# Connectors.net
KiCad netlist of a schematic drawn in Altium Designer
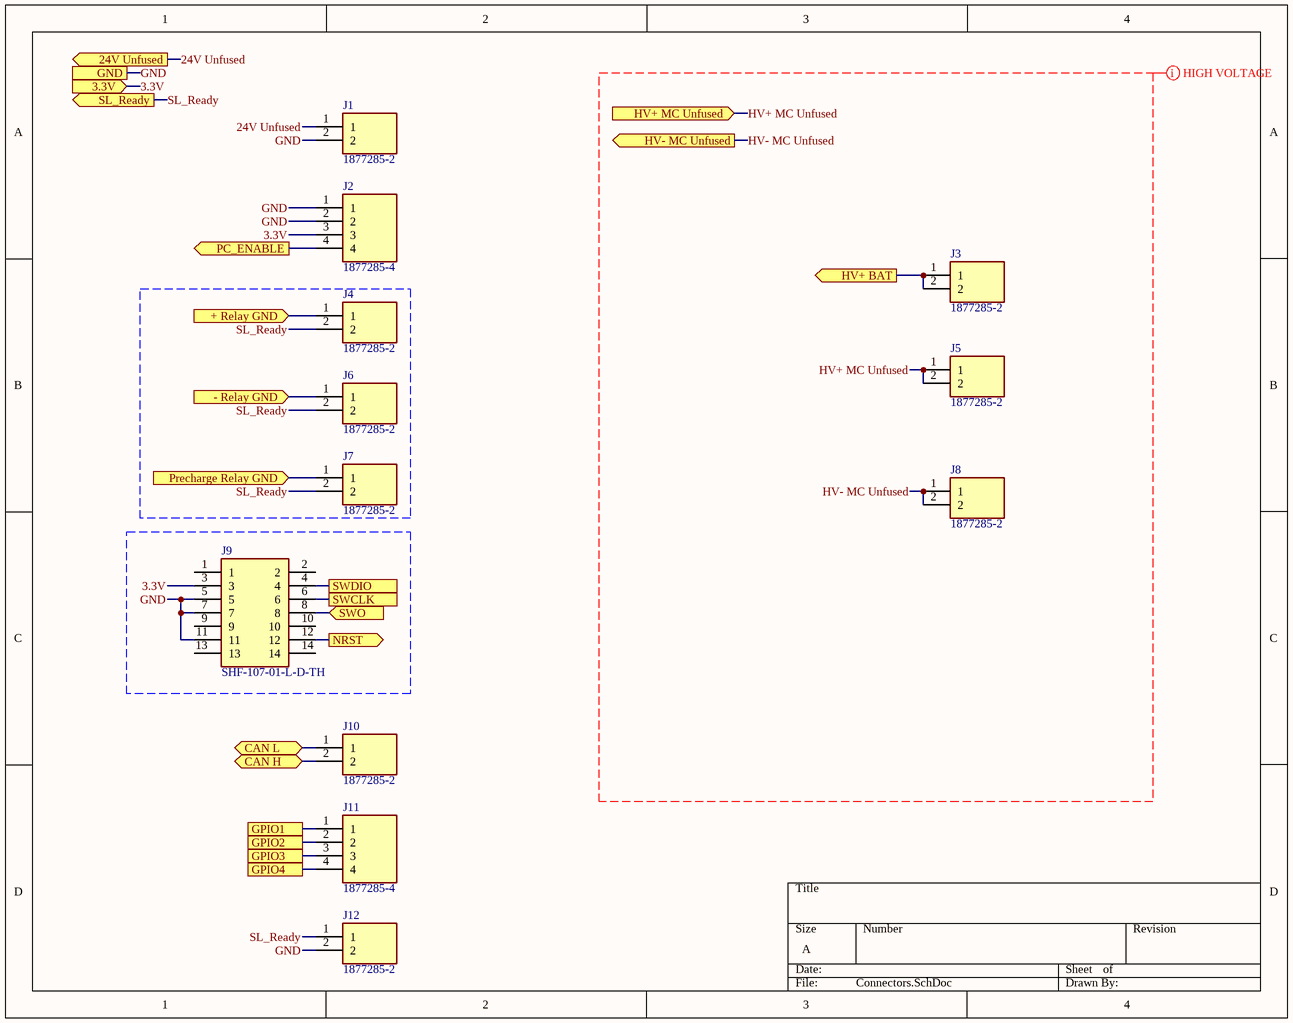
[diagram p0: Connectors.SchDoc]

(export (version "E")
  (design (tool "Eeschema 10.0.6"))
  (components
    (comp (ref "J1")
      (value "1877285-2")
      (footprint "SamacSys:18772852")
      (description "Connector")
      (fields (field (name "MOUSER PART NUMBER") "571-1877285-2"))
      (libsource (lib "SamacSys") (part "1877285-2"))
    )
    (comp (ref "J2")
      (value "1877285-4")
      (footprint "SamacSys:18772854")
      (description "Connector")
      (fields (field (name "MOUSER PART NUMBER") "571-1877285-4"))
      (libsource (lib "SamacSys") (part "1877285-4"))
    )
    (comp (ref "J3")
      (value "1877285-2")
      (footprint "SamacSys:18772852")
      (description "Connector")
      (fields (field (name "MOUSER PART NUMBER") "571-1877285-2"))
      (libsource (lib "SamacSys") (part "1877285-2"))
    )
    (comp (ref "J4")
      (value "1877285-2")
      (footprint "SamacSys:18772852")
      (description "Connector")
      (fields (field (name "MOUSER PART NUMBER") "571-1877285-2"))
      (libsource (lib "SamacSys") (part "1877285-2"))
    )
    (comp (ref "J5")
      (value "1877285-2")
      (footprint "SamacSys:18772852")
      (description "Connector")
      (fields (field (name "MOUSER PART NUMBER") "571-1877285-2"))
      (libsource (lib "SamacSys") (part "1877285-2"))
    )
    (comp (ref "J6")
      (value "1877285-2")
      (footprint "SamacSys:18772852")
      (description "Connector")
      (fields (field (name "MOUSER PART NUMBER") "571-1877285-2"))
      (libsource (lib "SamacSys") (part "1877285-2"))
    )
    (comp (ref "J7")
      (value "1877285-2")
      (footprint "SamacSys:18772852")
      (description "Connector")
      (fields (field (name "MOUSER PART NUMBER") "571-1877285-2"))
      (libsource (lib "SamacSys") (part "1877285-2"))
    )
    (comp (ref "J8")
      (value "1877285-2")
      (footprint "SamacSys:18772852")
      (description "Connector")
      (fields (field (name "MOUSER PART NUMBER") "571-1877285-2"))
      (libsource (lib "SamacSys") (part "1877285-2"))
    )
    (comp (ref "J9")
      (value "SHF-107-01-L-D-TH")
      (footprint "SamacSys:SHF10701LDTH")
      (description "Connector")
      (fields (field (name "MOUSER PART NUMBER") "200-SHF10701LDTH"))
      (libsource (lib "SamacSys") (part "SHF-107-01-L-D-TH"))
    )
    (comp (ref "J10")
      (value "1877285-2")
      (footprint "SamacSys:18772852")
      (description "Connector")
      (fields (field (name "MOUSER PART NUMBER") "571-1877285-2"))
      (libsource (lib "SamacSys") (part "1877285-2"))
    )
    (comp (ref "J11")
      (value "1877285-4")
      (footprint "SamacSys:18772854")
      (description "Connector")
      (fields (field (name "MOUSER PART NUMBER") "571-1877285-4"))
      (libsource (lib "SamacSys") (part "1877285-4"))
    )
    (comp (ref "J12")
      (value "1877285-2")
      (footprint "SamacSys:18772852")
      (description "Connector")
      (fields (field (name "MOUSER PART NUMBER") "571-1877285-2"))
      (libsource (lib "SamacSys") (part "1877285-2"))
    )
  )
  (nets
    (net (code "1") (name "/+ Relay GND") (class "Default")
      (node (ref "J4") (pin "1") (pinfunction "1_1") (pintype "passive"))
    )
    (net (code "2") (name "/- Relay GND") (class "Default")
      (node (ref "J6") (pin "1") (pinfunction "1_1") (pintype "passive"))
    )
    (net (code "3") (name "/3.3V") (class "Default")
      (node (ref "J2") (pin "3") (pinfunction "3_3") (pintype "passive"))
      (node (ref "J9") (pin "3") (pinfunction "3_3") (pintype "passive"))
    )
    (net (code "4") (name "/24V Unfused") (class "Default")
      (node (ref "J1") (pin "1") (pinfunction "1_1") (pintype "passive"))
    )
    (net (code "5") (name "/CAN H") (class "Default")
      (node (ref "J10") (pin "2") (pinfunction "2_2") (pintype "passive"))
    )
    (net (code "6") (name "/CAN L") (class "Default")
      (node (ref "J10") (pin "1") (pinfunction "1_1") (pintype "passive"))
    )
    (net (code "7") (name "/GND") (class "Default")
      (node (ref "J1") (pin "2") (pinfunction "2_2") (pintype "passive"))
      (node (ref "J12") (pin "2") (pinfunction "2_2") (pintype "passive"))
      (node (ref "J2") (pin "1") (pinfunction "1_1") (pintype "passive"))
      (node (ref "J2") (pin "2") (pinfunction "2_2") (pintype "passive"))
      (node (ref "J9") (pin "11") (pinfunction "11_11") (pintype "passive"))
      (node (ref "J9") (pin "5") (pinfunction "5_5") (pintype "passive"))
      (node (ref "J9") (pin "7") (pinfunction "7_7") (pintype "passive"))
    )
    (net (code "8") (name "/GPIO1") (class "Default")
      (node (ref "J11") (pin "1") (pinfunction "1_1") (pintype "passive"))
    )
    (net (code "9") (name "/GPIO2") (class "Default")
      (node (ref "J11") (pin "2") (pinfunction "2_2") (pintype "passive"))
    )
    (net (code "10") (name "/GPIO3") (class "Default")
      (node (ref "J11") (pin "3") (pinfunction "3_3") (pintype "passive"))
    )
    (net (code "11") (name "/GPIO4") (class "Default")
      (node (ref "J11") (pin "4") (pinfunction "4_4") (pintype "passive"))
    )
    (net (code "12") (name "/HV+ BAT") (class "Default")
      (node (ref "J3") (pin "1") (pinfunction "1_1") (pintype "passive"))
      (node (ref "J3") (pin "2") (pinfunction "2_2") (pintype "passive"))
    )
    (net (code "13") (name "/HV+ MC Unfused") (class "Default")
      (node (ref "J5") (pin "1") (pinfunction "1_1") (pintype "passive"))
      (node (ref "J5") (pin "2") (pinfunction "2_2") (pintype "passive"))
    )
    (net (code "14") (name "/HV- MC Unfused") (class "Default")
      (node (ref "J8") (pin "1") (pinfunction "1_1") (pintype "passive"))
      (node (ref "J8") (pin "2") (pinfunction "2_2") (pintype "passive"))
    )
    (net (code "15") (name "/NRST") (class "Default")
      (node (ref "J9") (pin "12") (pinfunction "12_12") (pintype "passive"))
    )
    (net (code "16") (name "/PC_ENABLE") (class "Default")
      (node (ref "J2") (pin "4") (pinfunction "4_4") (pintype "passive"))
    )
    (net (code "17") (name "/Precharge Relay GND") (class "Default")
      (node (ref "J7") (pin "1") (pinfunction "1_1") (pintype "passive"))
    )
    (net (code "18") (name "/SL_Ready") (class "Default")
      (node (ref "J12") (pin "1") (pinfunction "1_1") (pintype "passive"))
      (node (ref "J4") (pin "2") (pinfunction "2_2") (pintype "passive"))
      (node (ref "J6") (pin "2") (pinfunction "2_2") (pintype "passive"))
      (node (ref "J7") (pin "2") (pinfunction "2_2") (pintype "passive"))
    )
    (net (code "19") (name "/SWCLK") (class "Default")
      (node (ref "J9") (pin "6") (pinfunction "6_6") (pintype "passive"))
    )
    (net (code "20") (name "/SWDIO") (class "Default")
      (node (ref "J9") (pin "4") (pinfunction "4_4") (pintype "passive"))
    )
    (net (code "21") (name "/SWO") (class "Default")
      (node (ref "J9") (pin "8") (pinfunction "8_8") (pintype "passive"))
    )
    (net (code "22") (name "unconnected-(J9-Pad1)") (class "Default")
      (node (ref "J9") (pin "1") (pinfunction "1_1") (pintype "passive"))
    )
    (net (code "23") (name "unconnected-(J9-Pad2)") (class "Default")
      (node (ref "J9") (pin "2") (pinfunction "2_2") (pintype "passive"))
    )
    (net (code "24") (name "unconnected-(J9-Pad9)") (class "Default")
      (node (ref "J9") (pin "9") (pinfunction "9_9") (pintype "passive"))
    )
    (net (code "25") (name "unconnected-(J9-Pad10)") (class "Default")
      (node (ref "J9") (pin "10") (pinfunction "10_10") (pintype "passive"))
    )
    (net (code "26") (name "unconnected-(J9-Pad13)") (class "Default")
      (node (ref "J9") (pin "13") (pinfunction "13_13") (pintype "passive"))
    )
    (net (code "27") (name "unconnected-(J9-Pad14)") (class "Default")
      (node (ref "J9") (pin "14") (pinfunction "14_14") (pintype "passive"))
    )
  )
)
